# DCDCsim.net
KiCad netlist of a schematic drawn in Altium Designer
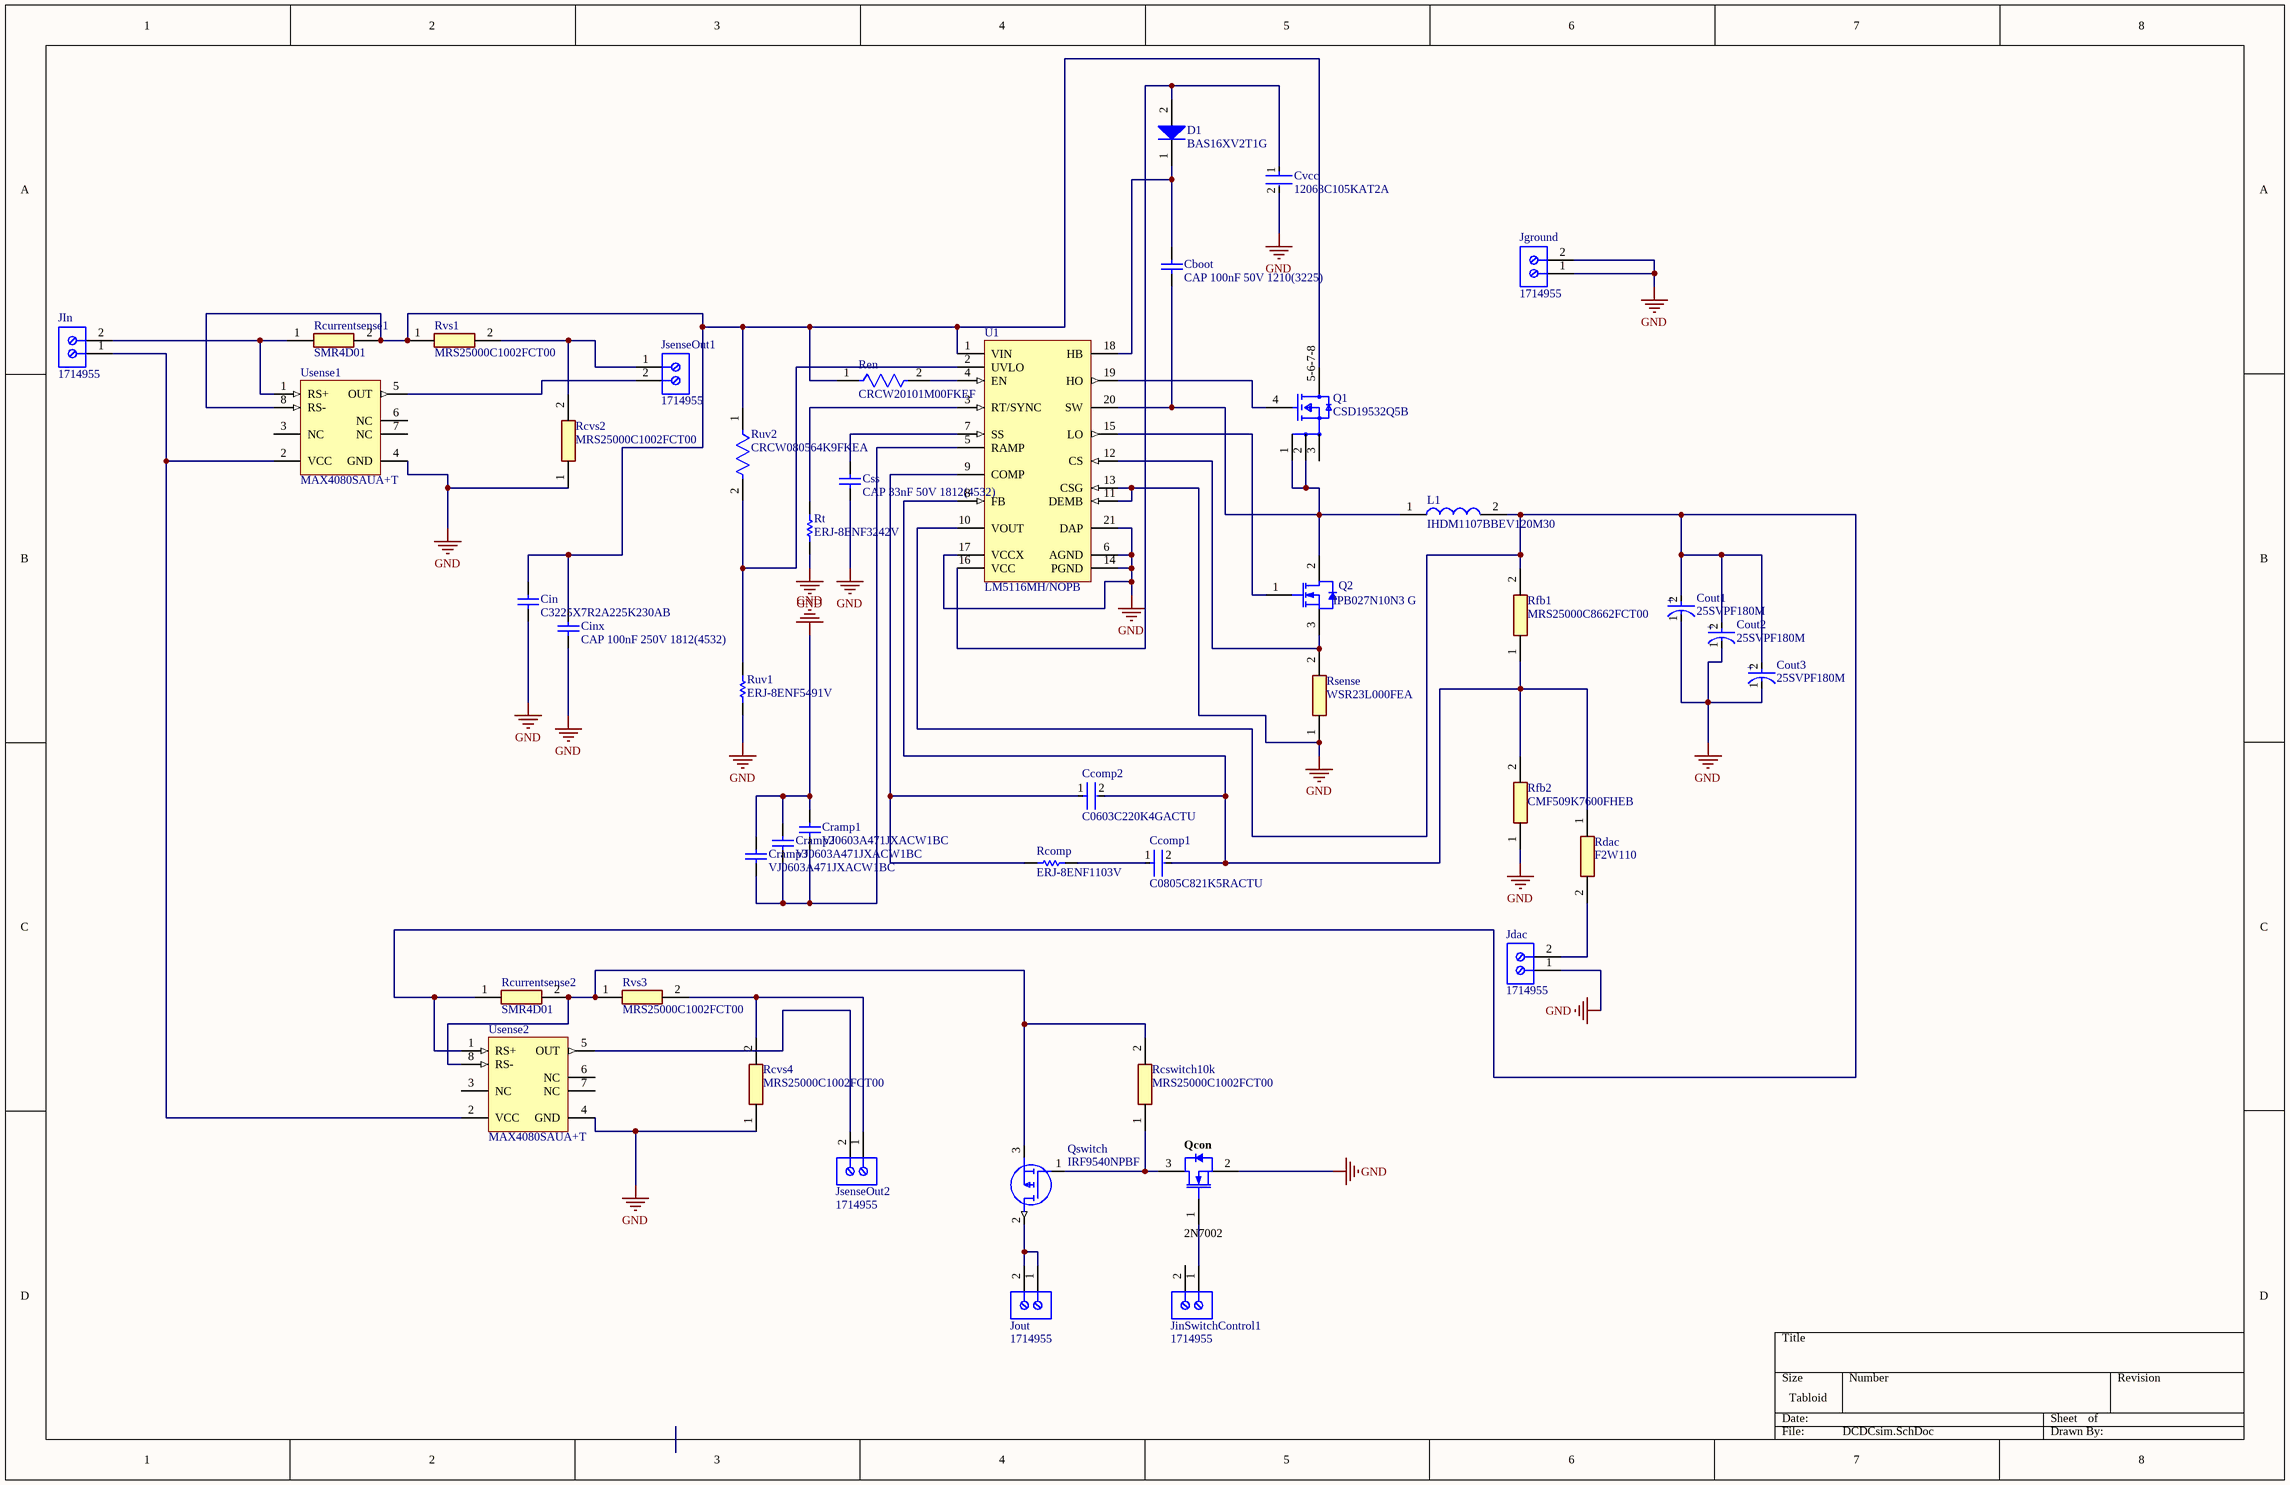
[diagram p0: DCDCsim.SchDoc]

(export (version "E")
  (design (tool "Eeschema 10.0.6"))
  (components
    (comp (ref "Cboot")
      (value "CAP 100nF 50V 1210(3225)")
      (footprint "CAPC1210(3225)155_M")
      (description "CAP 100nF 50V ±5% 1210 (3225 Metric) Thickness 1.45mm SMD")
      (fields (field (name "TOLERANCE") "Â±5%"))
      (libsource (lib "Altium Content Vault") (part "CAP"))
    )
    (comp (ref "Ccomp1")
      (value "C0805C821K5RACTU")
      (footprint "FP-C0805C-DN-MFG")
      (description "0805 C 820pF Ceramic Multilayer Capacitor; 50 VDC; +125degC; X7R Dielec; +/-10%")
      (fields (field (name "MANUFACTURER") "KEMET") (field (name "TOLERANCE") "0.1"))
      (libsource (lib "Altium Content Vault") (part "b4654b650e69147ec39a6b967a45e02"))
    )
    (comp (ref "Ccomp2")
      (value "C0603C220K4GACTU")
      (footprint "FP-C0603C-CF-MFG")
      (description "CAP CER 22PF 16V 10% NP0 0603")
      (fields
        (field (name "TOLERANCE") "0.1")
        (field (name "OCTOPART") "https://octopart.com/c0603c220k4gactu-kemet-17097913")
      )
      (libsource (lib "Altium Content Vault") (part "b4654b650e69147ec39a6b967a45e02"))
    )
    (comp (ref "Cin")
      (value "C3225X7R2A225K230AB")
      (footprint "CAPC3225X250X20LL40")
      (description "Chip Capacitor, 2.2 uF, +/- 10%, -55 to 125 degC, 1210 (3225 Metric), RoHS, Tape and Reel")
      (fields
        (field (name "PCN PART NUMBER") "MLCCPartNumberChange30/Nov/2012")
        (field (name "MANUFACTURER") "TDK")
      )
      (libsource (lib "Altium Content Vault") (part "CAP-NP-2"))
    )
    (comp (ref "Cinx")
      (value "CAP 100nF 250V 1812(4532)")
      (footprint "CAPC1812(4532)230_M")
      (description "CAP 100nF 250V ±10% 1812 (4532 Metric) Thickness 2.3mm SMD")
      (fields (field (name "TOLERANCE") "Â±10%"))
      (libsource (lib "Altium Content Vault") (part "CAP"))
    )
    (comp (ref "Cout1")
      (value "25SVPF180M")
      (footprint "FP-OS-CON-SMT-E12-MFG")
      (description "Conductive Polymer Aluminum Solid Capacitors (OS-CON) 180uF ±20% 25V")
      (fields (field (name "VOLTAGE") "25V") (field (name "TOLERANCE") "20%"))
      (libsource (lib "Altium Content Vault") (part "a00bbbee19879c290e62620ae7e47b1"))
    )
    (comp (ref "Cout2")
      (value "25SVPF180M")
      (footprint "FP-OS-CON-SMT-E12-MFG")
      (description "Conductive Polymer Aluminum Solid Capacitors (OS-CON) 180uF ±20% 25V")
      (fields (field (name "VOLTAGE") "25V") (field (name "TOLERANCE") "20%"))
      (libsource (lib "Altium Content Vault") (part "a00bbbee19879c290e62620ae7e47b1"))
    )
    (comp (ref "Cout3")
      (value "25SVPF180M")
      (footprint "FP-OS-CON-SMT-E12-MFG")
      (description "Conductive Polymer Aluminum Solid Capacitors (OS-CON) 180uF ±20% 25V")
      (fields (field (name "VOLTAGE") "25V") (field (name "TOLERANCE") "20%"))
      (libsource (lib "Altium Content Vault") (part "a00bbbee19879c290e62620ae7e47b1"))
    )
    (comp (ref "Cramp1")
      (value "VJ0603A471JXACW1BC")
      (footprint "CAPC1608X87X40ML10T15")
      (fields (field (name "MANUFACTURER") "Vitramon"))
      (libsource (lib "Altium Content Vault") (part "CAP"))
    )
    (comp (ref "Cramp2")
      (value "VJ0603A471JXACW1BC")
      (footprint "CAPC1608X87X40ML10T15")
      (fields (field (name "MANUFACTURER") "Vitramon"))
      (libsource (lib "Altium Content Vault") (part "CAP"))
    )
    (comp (ref "Cramp3")
      (value "VJ0603A471JXACW1BC")
      (footprint "CAPC1608X87X40ML10T15")
      (fields (field (name "MANUFACTURER") "Vitramon"))
      (libsource (lib "Altium Content Vault") (part "CAP"))
    )
    (comp (ref "Css")
      (value "CAP 33nF 50V 1812(4532)")
      (footprint "CAPC1812(4532)125_M")
      (description "CAP 33nF 50V ±5% 1812 (4532 Metric) Thickness 1.25mm SMD")
      (fields (field (name "TOLERANCE") "Â±5%"))
      (libsource (lib "Altium Content Vault") (part "CAP"))
    )
    (comp (ref "Cvcc")
      (value "12063C105KAT2A")
      (footprint "FP-1206-L_3_2_0_2-W_1_6_0-IPC_A")
      (description "General Purpose Ceramic Capacitor, 1206, 1uF, 10%, X7R, 15%, 25V")
      (fields (field (name "TOLERANCE") "10%") (field (name "VOLTAGE") "25V"))
      (libsource (lib "Altium Content Vault") (part "b4654b650e69147ec39a6b967a45e02"))
    )
    (comp (ref "D1")
      (value "BAS16XV2T1G")
      (footprint "ONSC-SOD-523-2-502-01_V")
      (description "Switching Diode, 2-Pin SOD-523, Pb-Free, Tape and Reel")
      (fields (field (name "MANUFACTURER") "On Semiconductor"))
      (libsource (lib "Altium Content Vault") (part "ONSC-D-K1A2-2"))
    )
    (comp (ref "Jdac")
      (value "1714955")
      (footprint "PHOE-1714955_V")
      (description "PC Terminal Block, Pitch 6.35 mm, 1 x 2 Position, Height 21.5 mm, Tail Lenght 5.1 mm, RoHS, Bulk")
      (fields (field (name "MANUFACTURER") "Phoenix Contact"))
      (libsource (lib "Altium Content Vault") (part "CN-1P-F-TB2"))
    )
    (comp (ref "Jground")
      (value "1714955")
      (footprint "PHOE-1714955_V")
      (description "PC Terminal Block, Pitch 6.35 mm, 1 x 2 Position, Height 21.5 mm, Tail Lenght 5.1 mm, RoHS, Bulk")
      (fields (field (name "MANUFACTURER") "Phoenix Contact"))
      (libsource (lib "Altium Content Vault") (part "CN-1P-F-TB2"))
    )
    (comp (ref "JIn")
      (value "1714955")
      (footprint "PHOE-1714955_V")
      (description "PC Terminal Block, Pitch 6.35 mm, 1 x 2 Position, Height 21.5 mm, Tail Lenght 5.1 mm, RoHS, Bulk")
      (fields (field (name "MANUFACTURER") "Phoenix Contact"))
      (libsource (lib "Altium Content Vault") (part "CN-1P-F-TB2"))
    )
    (comp (ref "JinSwitchControl1")
      (value "1714955")
      (footprint "PHOE-1714955_V")
      (description "PC Terminal Block, Pitch 6.35 mm, 1 x 2 Position, Height 21.5 mm, Tail Lenght 5.1 mm, RoHS, Bulk")
      (fields (field (name "MANUFACTURER") "Phoenix Contact"))
      (libsource (lib "Altium Content Vault") (part "CN-1P-F-TB2"))
    )
    (comp (ref "Jout")
      (value "1714955")
      (footprint "PHOE-1714955_V")
      (description "PC Terminal Block, Pitch 6.35 mm, 1 x 2 Position, Height 21.5 mm, Tail Lenght 5.1 mm, RoHS, Bulk")
      (fields (field (name "MANUFACTURER") "Phoenix Contact"))
      (libsource (lib "Altium Content Vault") (part "CN-1P-F-TB2"))
    )
    (comp (ref "JsenseOut1")
      (value "1714955")
      (footprint "PHOE-1714955_V")
      (description "PC Terminal Block, Pitch 6.35 mm, 1 x 2 Position, Height 21.5 mm, Tail Lenght 5.1 mm, RoHS, Bulk")
      (fields (field (name "MANUFACTURER") "Phoenix Contact"))
      (libsource (lib "Altium Content Vault") (part "CN-1P-F-TB2"))
    )
    (comp (ref "JsenseOut2")
      (value "1714955")
      (footprint "PHOE-1714955_V")
      (description "PC Terminal Block, Pitch 6.35 mm, 1 x 2 Position, Height 21.5 mm, Tail Lenght 5.1 mm, RoHS, Bulk")
      (fields (field (name "MANUFACTURER") "Phoenix Contact"))
      (libsource (lib "Altium Content Vault") (part "CN-1P-F-TB2"))
    )
    (comp (ref "L1")
      (value "IHDM1107BBEV120M30")
      (footprint "SamacSys:IHDM1107BBEV120M30")
      (description "Inductor")
      (fields (field (name "MOUSER PART NUMBER") "70-IHDM1107BBV120M30"))
      (libsource (lib "*") (part "IHDM1107BBEV120M30"))
    )
    (comp (ref "Q1")
      (value "CSD19532Q5B")
      (footprint "FP-DNK0008A-MFG")
      (description "MOSFET N-CH 100V 100A 8SON")
      (fields
        (field (name "OCTOPART") "https://octopart.com/csd19532q5b-texas+instruments-32890191")
        (field (name "MANUFACTURER") "Texas Instruments")
      )
      (libsource (lib "Altium Content Vault") (part "6fb2c024a3b9031f6d89538bc87a0fd"))
    )
    (comp (ref "Q2")
      (value "IPB027N10N3 G")
      (footprint "INF-PG-TO-263-3-2_A_N")
      (fields (field (name "MANUFACTURER") "Infineon"))
      (libsource (lib "Altium Content Vault") (part "INF-NEMOS-GDS-3"))
    )
    (comp (ref "Qcon")
      (value "2N7002")
      (footprint "INF-PG-SOT23_M")
      (fields (field (name "MANUFACTURER") "Infineon"))
      (libsource (lib "Altium Content Vault") (part "INF-NDMOS-GSD-3"))
    )
    (comp (ref "Qswitch")
      (value "IRF9540NPBF")
      (footprint "SamacSys:TO254P469X1042X1967-3P")
      (description "MOSFET (P-Channel)")
      (fields (field (name "MOUSER PART NUMBER") "942-IRF9540NPBF"))
      (libsource (lib "*") (part "IRF9540NPBF"))
    )
    (comp (ref "Rcomp")
      (value "ERJ-8ENF1103V")
      (footprint "RESC3216X70X50LL05T20")
      (fields (field (name "MANUFACTURER") "Panasonic"))
      (libsource (lib "Altium Content Vault") (part "RES"))
    )
    (comp (ref "Rcswitch10k")
      (value "MRS25000C1002FCT00")
      (footprint "SamacSys:RESAD1650W60L650D250")
      (description "Resistor")
      (fields (field (name "MOUSER PART NUMBER") "594-MRS25000C1002FCT"))
      (libsource (lib "*") (part "MRS25000C1002FCT00"))
    )
    (comp (ref "Rcurrentsense1")
      (value "SMR4D01")
      (footprint "SamacSys:SMR4D01")
      (description "Resistor")
      (libsource (lib "*") (part "SMR4D01"))
    )
    (comp (ref "Rcurrentsense2")
      (value "SMR4D01")
      (footprint "SamacSys:SMR4D01")
      (description "Resistor")
      (libsource (lib "*") (part "SMR4D01"))
    )
    (comp (ref "Rcvs2")
      (value "MRS25000C1002FCT00")
      (footprint "SamacSys:RESAD1650W60L650D250")
      (description "Resistor")
      (fields (field (name "MOUSER PART NUMBER") "594-MRS25000C1002FCT"))
      (libsource (lib "*") (part "MRS25000C1002FCT00"))
    )
    (comp (ref "Rcvs4")
      (value "MRS25000C1002FCT00")
      (footprint "SamacSys:RESAD1650W60L650D250")
      (description "Resistor")
      (fields (field (name "MOUSER PART NUMBER") "594-MRS25000C1002FCT"))
      (libsource (lib "*") (part "MRS25000C1002FCT00"))
    )
    (comp (ref "Rdac")
      (value "F2W110")
      (footprint "SamacSys:RESAD2780W70L1140D410")
      (description "Resistor")
      (libsource (lib "*") (part "F2W110"))
    )
    (comp (ref "Ren")
      (value "CRCW20101M00FKEF")
      (footprint "FP-CRCW2010-e3-MFG")
      (description "RES Thick Film, 1MΩ, 1%, 0.75W, 100ppm/°C, 2010")
      (fields (field (name "TOLERANCE") "1%"))
      (libsource (lib "Altium Content Vault") (part "1029c3af85768c4190bb7ad29bc67b5"))
    )
    (comp (ref "Rfb1")
      (value "MRS25000C8662FCT00")
      (footprint "SamacSys:RESAD1650W60L650D250")
      (description "Resistor")
      (libsource (lib "*") (part "MRS25000C8662FCT00"))
    )
    (comp (ref "Rfb2")
      (value "CMF509K7600FHEB")
      (footprint "SamacSys:RESAD1041W46L381D165")
      (description "Resistor")
      (libsource (lib "*") (part "CMF509K7600FHEB"))
    )
    (comp (ref "Rsense")
      (value "WSR23L000FEA")
      (footprint "SamacSys:RESC11670X254N")
      (description "Resistor")
      (libsource (lib "*") (part "WSR23L000FEA"))
    )
    (comp (ref "Rt")
      (value "ERJ-8ENF3242V")
      (footprint "RESC3216X70X50NL05T20")
      (fields (field (name "MANUFACTURER") "Panasonic"))
      (libsource (lib "Altium Content Vault") (part "RES"))
    )
    (comp (ref "Ruv1")
      (value "ERJ-8ENF5491V")
      (footprint "RESC3216X70X50NL05T20")
      (fields (field (name "MANUFACTURER") "Panasonic"))
      (libsource (lib "Altium Content Vault") (part "RES"))
    )
    (comp (ref "Ruv2")
      (value "CRCW080564K9FKEA")
      (footprint "FP-CRCW0805-e3-IPC_C")
      (description "RES Thick Film, 64.9kΩ, 1%, 0.125W, 100ppm/°C, 0805")
      (fields (field (name "TOLERANCE") "1%"))
      (libsource (lib "Altium Content Vault") (part "1029c3af85768c4190bb7ad29bc67b5"))
    )
    (comp (ref "Rvs1")
      (value "MRS25000C1002FCT00")
      (footprint "SamacSys:RESAD1650W60L650D250")
      (description "Resistor")
      (fields (field (name "MOUSER PART NUMBER") "594-MRS25000C1002FCT"))
      (libsource (lib "") (part "MRS25000C1002FCT00_1"))
    )
    (comp (ref "Rvs3")
      (value "MRS25000C1002FCT00")
      (footprint "SamacSys:RESAD1650W60L650D250")
      (description "Resistor")
      (fields (field (name "MOUSER PART NUMBER") "594-MRS25000C1002FCT"))
      (libsource (lib "") (part "MRS25000C1002FCT00_1"))
    )
    (comp (ref "U1")
      (value "LM5116MH/NOPB")
      (footprint "PWP0020A_N")
      (description "Wide Range Synchronous Buck Controller, 20-pin TSSOP-EP, Pb-Free")
      (fields (field (name "MANUFACTURER") "Texas Instruments"))
      (libsource (lib "Altium Content Vault") (part "PM-REG-LM5116MH"))
    )
    (comp (ref "Usense1")
      (value "MAX4080SAUA+T")
      (footprint "MAXM-U8+1_L")
      (libsource (lib "Altium Content Vault") (part "MAX4080-X8_1_2"))
    )
    (comp (ref "Usense2")
      (value "MAX4080SAUA+T")
      (footprint "MAXM-U8+1_L")
      (libsource (lib "Altium Content Vault") (part "MAX4080-X8_1_2"))
    )
  )
  (nets
    (net (code "1") (name "GND") (class "Default")
      (node (ref "Cin") (pin "1") (pinfunction "1_1") (pintype "passive"))
      (node (ref "Cinx") (pin "1") (pinfunction "1_1") (pintype "passive"))
      (node (ref "Cout1") (pin "1") (pinfunction "C_1") (pintype "passive"))
      (node (ref "Cout2") (pin "1") (pinfunction "C_1") (pintype "passive"))
      (node (ref "Cout3") (pin "1") (pinfunction "C_1") (pintype "passive"))
      (node (ref "Cramp1") (pin "2") (pinfunction "2_2") (pintype "passive"))
      (node (ref "Cramp2") (pin "2") (pinfunction "2_2") (pintype "passive"))
      (node (ref "Cramp3") (pin "2") (pinfunction "2_2") (pintype "passive"))
      (node (ref "Css") (pin "1") (pinfunction "1_1") (pintype "passive"))
      (node (ref "Cvcc") (pin "2") (pinfunction "2_2") (pintype "passive"))
      (node (ref "Jdac") (pin "1") (pinfunction "1_1") (pintype "passive"))
      (node (ref "Jground") (pin "1") (pinfunction "1_1") (pintype "passive"))
      (node (ref "Jground") (pin "2") (pinfunction "2_2") (pintype "passive"))
      (node (ref "Qcon") (pin "2") (pinfunction "SOURCE_2") (pintype "passive"))
      (node (ref "Rcvs2") (pin "1") (pinfunction "1_1") (pintype "passive"))
      (node (ref "Rcvs4") (pin "1") (pinfunction "1_1") (pintype "passive"))
      (node (ref "Rfb2") (pin "1") (pinfunction "1_1") (pintype "passive"))
      (node (ref "Rsense") (pin "1") (pinfunction "1_1") (pintype "passive"))
      (node (ref "Rt") (pin "1") (pinfunction "1_1") (pintype "passive"))
      (node (ref "Ruv1") (pin "1") (pinfunction "1_1") (pintype "passive"))
      (node (ref "U1") (pin "11") (pinfunction "DEMB_11") (pintype "input"))
      (node (ref "U1") (pin "13") (pinfunction "CSG_13") (pintype "input"))
      (node (ref "U1") (pin "14") (pinfunction "PGND_14") (pintype "power_in"))
      (node (ref "U1") (pin "17") (pinfunction "VCCX_17") (pintype "power_in"))
      (node (ref "U1") (pin "21") (pinfunction "DAP_21") (pintype "power_in"))
      (node (ref "U1") (pin "6") (pinfunction "AGND_6") (pintype "power_in"))
      (node (ref "Usense1") (pin "4") (pinfunction "GND_4") (pintype "power_in"))
      (node (ref "Usense2") (pin "4") (pinfunction "GND_4") (pintype "power_in"))
    )
    (net (code "2") (name "Net-(Ccomp1-Pad1)") (class "Default")
      (node (ref "Ccomp1") (pin "1") (pinfunction "1_1") (pintype "passive"))
      (node (ref "Rcomp") (pin "2") (pinfunction "2_2") (pintype "passive"))
    )
    (net (code "3") (name "Net-(Cout1-A)") (class "Default")
      (node (ref "Cout1") (pin "2") (pinfunction "A_2") (pintype "passive"))
      (node (ref "Cout2") (pin "2") (pinfunction "A_2") (pintype "passive"))
      (node (ref "Cout3") (pin "2") (pinfunction "A_2") (pintype "passive"))
      (node (ref "L1") (pin "2") (pinfunction "2_2") (pintype "passive"))
      (node (ref "Rcurrentsense2") (pin "1") (pinfunction "1_1") (pintype "passive"))
      (node (ref "Rfb1") (pin "2") (pinfunction "2_2") (pintype "passive"))
      (node (ref "U1") (pin "10") (pinfunction "VOUT_10") (pintype "passive"))
      (node (ref "Usense2") (pin "1") (pinfunction "RS+_1") (pintype "input"))
    )
    (net (code "4") (name "Net-(D1-A)") (class "Default")
      (node (ref "Cvcc") (pin "1") (pinfunction "1_1") (pintype "passive"))
      (node (ref "D1") (pin "2") (pinfunction "A_2") (pintype "passive"))
      (node (ref "U1") (pin "16") (pinfunction "VCC_16") (pintype "power_in"))
    )
    (net (code "5") (name "Net-(D1-K)") (class "Default")
      (node (ref "Cboot") (pin "2") (pinfunction "2_2") (pintype "passive"))
      (node (ref "D1") (pin "1") (pinfunction "K_1") (pintype "passive"))
      (node (ref "U1") (pin "18") (pinfunction "HB_18") (pintype "passive"))
    )
    (net (code "6") (name "Net-(Jdac-Pad2)") (class "Default")
      (node (ref "Jdac") (pin "2") (pinfunction "2_2") (pintype "passive"))
      (node (ref "Rdac") (pin "2") (pinfunction "2_2") (pintype "passive"))
    )
    (net (code "7") (name "Net-(JsenseOut1-Pad1)") (class "Default")
      (node (ref "JsenseOut1") (pin "1") (pinfunction "1_1") (pintype "passive"))
      (node (ref "Rcvs2") (pin "2") (pinfunction "2_2") (pintype "passive"))
      (node (ref "Rvs1") (pin "2") (pinfunction "2_2") (pintype "passive"))
    )
    (net (code "8") (name "Net-(JsenseOut2-Pad1)") (class "Default")
      (node (ref "JsenseOut2") (pin "1") (pinfunction "1_1") (pintype "passive"))
      (node (ref "Rcvs4") (pin "2") (pinfunction "2_2") (pintype "passive"))
      (node (ref "Rvs3") (pin "2") (pinfunction "2_2") (pintype "passive"))
    )
    (net (code "9") (name "Net-(Q1-D)") (class "Default")
      (node (ref "Cin") (pin "2") (pinfunction "2_2") (pintype "passive"))
      (node (ref "Cinx") (pin "2") (pinfunction "2_2") (pintype "passive"))
      (node (ref "Q1") (pin "5-6-7-8") (pinfunction "D_5-6-7-8") (pintype "passive"))
      (node (ref "Rcurrentsense1") (pin "2") (pinfunction "2_2") (pintype "passive"))
      (node (ref "Ren") (pin "1") (pinfunction "1_1") (pintype "passive"))
      (node (ref "Ruv2") (pin "1") (pinfunction "1_1") (pintype "passive"))
      (node (ref "Rvs1") (pin "1") (pinfunction "1_1") (pintype "passive"))
      (node (ref "U1") (pin "1") (pinfunction "VIN_1") (pintype "power_in"))
      (node (ref "Usense1") (pin "8") (pinfunction "RS-_8") (pintype "input"))
    )
    (net (code "10") (name "Net-(Q1-G)") (class "Default")
      (node (ref "Q1") (pin "4") (pinfunction "G_4") (pintype "passive"))
      (node (ref "U1") (pin "19") (pinfunction "HO_19") (pintype "output"))
    )
    (net (code "11") (name "Net-(Q2-DRAIN)") (class "Default")
      (node (ref "Cboot") (pin "1") (pinfunction "1_1") (pintype "passive"))
      (node (ref "L1") (pin "1") (pinfunction "1_1") (pintype "passive"))
      (node (ref "Q1") (pin "1") (pinfunction "S_1") (pintype "passive"))
      (node (ref "Q1") (pin "2") (pinfunction "S_2") (pintype "passive"))
      (node (ref "Q2") (pin "2") (pinfunction "DRAIN_2") (pintype "passive"))
      (node (ref "U1") (pin "20") (pinfunction "SW_20") (pintype "power_in"))
    )
    (net (code "12") (name "Net-(Q2-GATE)") (class "Default")
      (node (ref "Q2") (pin "1") (pinfunction "GATE_1") (pintype "passive"))
      (node (ref "U1") (pin "15") (pinfunction "LO_15") (pintype "output"))
    )
    (net (code "13") (name "Net-(Q2-SOURCE)") (class "Default")
      (node (ref "Q2") (pin "3") (pinfunction "SOURCE_3") (pintype "passive"))
      (node (ref "Rsense") (pin "2") (pinfunction "2_2") (pintype "passive"))
      (node (ref "U1") (pin "12") (pinfunction "CS_12") (pintype "input"))
    )
    (net (code "14") (name "Net-(Qcon-DRAIN)") (class "Default")
      (node (ref "Qcon") (pin "3") (pinfunction "DRAIN_3") (pintype "passive"))
      (node (ref "Qswitch") (pin "1") (pinfunction "G_1") (pintype "power_in"))
      (node (ref "Rcswitch10k") (pin "1") (pinfunction "1_1") (pintype "passive"))
    )
    (net (code "15") (name "Net-(Qcon-GATE)") (class "Default")
      (node (ref "JinSwitchControl1") (pin "1") (pinfunction "1_1") (pintype "passive"))
      (node (ref "Qcon") (pin "1") (pinfunction "GATE_1") (pintype "passive"))
    )
    (net (code "16") (name "Net-(Qswitch-D)") (class "Default")
      (node (ref "Jout") (pin "1") (pinfunction "1_1") (pintype "passive"))
      (node (ref "Jout") (pin "2") (pinfunction "2_2") (pintype "passive"))
      (node (ref "Qswitch") (pin "2") (pinfunction "D_2") (pintype "output"))
    )
    (net (code "17") (name "Net-(Qswitch-S)") (class "Default")
      (node (ref "Qswitch") (pin "3") (pinfunction "S_3") (pintype "power_in"))
      (node (ref "Rcswitch10k") (pin "2") (pinfunction "2_2") (pintype "passive"))
      (node (ref "Rcurrentsense2") (pin "2") (pinfunction "2_2") (pintype "passive"))
      (node (ref "Rvs3") (pin "1") (pinfunction "1_1") (pintype "passive"))
      (node (ref "Usense2") (pin "8") (pinfunction "RS-_8") (pintype "input"))
    )
    (net (code "18") (name "Net-(U1-COMP)") (class "Default")
      (node (ref "Ccomp2") (pin "1") (pinfunction "1_1") (pintype "passive"))
      (node (ref "Rcomp") (pin "1") (pinfunction "1_1") (pintype "passive"))
      (node (ref "U1") (pin "9") (pinfunction "COMP_9") (pintype "passive"))
    )
    (net (code "19") (name "Net-(U1-EN)") (class "Default")
      (node (ref "Ren") (pin "2") (pinfunction "2_2") (pintype "passive"))
      (node (ref "U1") (pin "4") (pinfunction "EN_4") (pintype "input"))
    )
    (net (code "20") (name "Net-(U1-FB)") (class "Default")
      (node (ref "Ccomp1") (pin "2") (pinfunction "2_2") (pintype "passive"))
      (node (ref "Ccomp2") (pin "2") (pinfunction "2_2") (pintype "passive"))
      (node (ref "Rdac") (pin "1") (pinfunction "1_1") (pintype "passive"))
      (node (ref "Rfb1") (pin "1") (pinfunction "1_1") (pintype "passive"))
      (node (ref "Rfb2") (pin "2") (pinfunction "2_2") (pintype "passive"))
      (node (ref "U1") (pin "8") (pinfunction "FB_8") (pintype "input"))
    )
    (net (code "21") (name "Net-(U1-RAMP)") (class "Default")
      (node (ref "Cramp1") (pin "1") (pinfunction "1_1") (pintype "passive"))
      (node (ref "Cramp2") (pin "1") (pinfunction "1_1") (pintype "passive"))
      (node (ref "Cramp3") (pin "1") (pinfunction "1_1") (pintype "passive"))
      (node (ref "U1") (pin "5") (pinfunction "RAMP_5") (pintype "passive"))
    )
    (net (code "22") (name "Net-(U1-RT{slash}SYNC)") (class "Default")
      (node (ref "Rt") (pin "2") (pinfunction "2_2") (pintype "passive"))
      (node (ref "U1") (pin "3") (pinfunction "RT/SYNC_3") (pintype "input"))
    )
    (net (code "23") (name "Net-(U1-SS)") (class "Default")
      (node (ref "Css") (pin "2") (pinfunction "2_2") (pintype "passive"))
      (node (ref "U1") (pin "7") (pinfunction "SS_7") (pintype "input"))
    )
    (net (code "24") (name "Net-(U1-UVLO)") (class "Default")
      (node (ref "Ruv1") (pin "2") (pinfunction "2_2") (pintype "passive"))
      (node (ref "Ruv2") (pin "2") (pinfunction "2_2") (pintype "passive"))
      (node (ref "U1") (pin "2") (pinfunction "UVLO_2") (pintype "passive"))
    )
    (net (code "25") (name "Net-(Usense1-OUT)") (class "Default")
      (node (ref "JsenseOut1") (pin "2") (pinfunction "2_2") (pintype "passive"))
      (node (ref "Usense1") (pin "5") (pinfunction "OUT_5") (pintype "output"))
    )
    (net (code "26") (name "Net-(Usense1-RS+)") (class "Default")
      (node (ref "JIn") (pin "2") (pinfunction "2_2") (pintype "passive"))
      (node (ref "Rcurrentsense1") (pin "1") (pinfunction "1_1") (pintype "passive"))
      (node (ref "Usense1") (pin "1") (pinfunction "RS+_1") (pintype "input"))
    )
    (net (code "27") (name "Net-(Usense1-VCC)") (class "Default")
      (node (ref "JIn") (pin "1") (pinfunction "1_1") (pintype "passive"))
      (node (ref "Usense1") (pin "2") (pinfunction "VCC_2") (pintype "power_in"))
      (node (ref "Usense2") (pin "2") (pinfunction "VCC_2") (pintype "power_in"))
    )
    (net (code "28") (name "Net-(Usense2-OUT)") (class "Default")
      (node (ref "JsenseOut2") (pin "2") (pinfunction "2_2") (pintype "passive"))
      (node (ref "Usense2") (pin "5") (pinfunction "OUT_5") (pintype "output"))
    )
    (net (code "29") (name "unconnected-(JinSwitchControl1-Pad2)") (class "Default")
      (node (ref "JinSwitchControl1") (pin "2") (pinfunction "2_2") (pintype "passive"))
    )
    (net (code "30") (name "unconnected-(Q1-S-Pad3)") (class "Default")
      (node (ref "Q1") (pin "3") (pinfunction "S_3") (pintype "passive"))
    )
    (net (code "31") (name "unconnected-(Usense1-NC-Pad3)") (class "Default")
      (node (ref "Usense1") (pin "3") (pinfunction "NC_3") (pintype "passive"))
    )
    (net (code "32") (name "unconnected-(Usense1-NC-Pad6)") (class "Default")
      (node (ref "Usense1") (pin "6") (pinfunction "NC_6") (pintype "passive"))
    )
    (net (code "33") (name "unconnected-(Usense1-NC-Pad7)") (class "Default")
      (node (ref "Usense1") (pin "7") (pinfunction "NC_7") (pintype "passive"))
    )
    (net (code "34") (name "unconnected-(Usense2-NC-Pad3)") (class "Default")
      (node (ref "Usense2") (pin "3") (pinfunction "NC_3") (pintype "passive"))
    )
    (net (code "35") (name "unconnected-(Usense2-NC-Pad6)") (class "Default")
      (node (ref "Usense2") (pin "6") (pinfunction "NC_6") (pintype "passive"))
    )
    (net (code "36") (name "unconnected-(Usense2-NC-Pad7)") (class "Default")
      (node (ref "Usense2") (pin "7") (pinfunction "NC_7") (pintype "passive"))
    )
  )
)
